# Switch_Board.net
KiCad netlist of a schematic drawn in Altium Designer
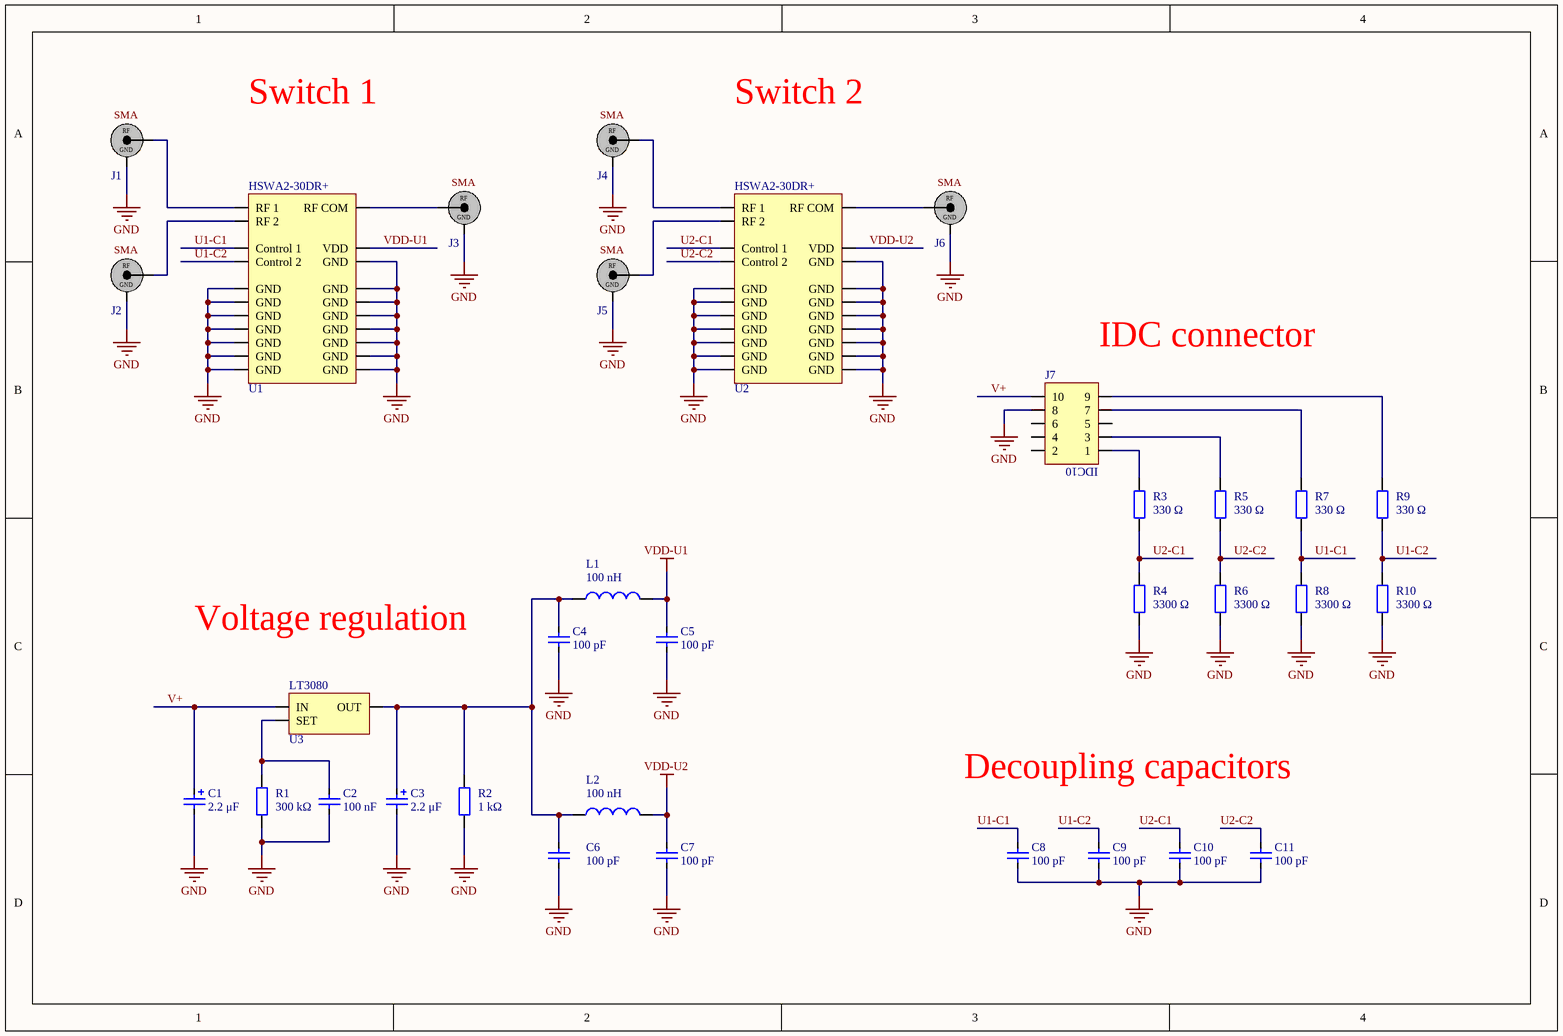
[diagram p0: Switch_Board.SchDoc]

(export (version "E")
  (design (tool "Eeschema 10.0.6"))
  (components
    (comp (ref "C1")
      (value "2.2 μF")
      (footprint "EIA 3528-21")
      (description "General symbol for a surface-mount polarized capacitor")
      (fields (field (name "Comment") "Capacitor (polarized)"))
      (libsource (lib "Switch_System") (part "Capacitor (polarized)"))
    )
    (comp (ref "C2")
      (value "100 nF")
      (footprint "0603C")
      (description "General symbol for a surface-mount capacitor")
      (fields (field (name "Comment") "Capacitor"))
      (libsource (lib "Switch_System") (part "Capacitor"))
    )
    (comp (ref "C3")
      (value "2.2 μF")
      (footprint "EIA 3528-21")
      (description "General symbol for a surface-mount polarized capacitor")
      (fields (field (name "Comment") "Capacitor (polarized)"))
      (libsource (lib "Switch_System") (part "Capacitor (polarized)"))
    )
    (comp (ref "C4")
      (value "100 pF")
      (footprint "0603C")
      (description "General symbol for a surface-mount capacitor")
      (fields (field (name "Comment") "Capacitor"))
      (libsource (lib "Switch_System") (part "Capacitor"))
    )
    (comp (ref "C5")
      (value "100 pF")
      (footprint "0603C")
      (description "General symbol for a surface-mount capacitor")
      (fields (field (name "Comment") "Capacitor"))
      (libsource (lib "Switch_System") (part "Capacitor"))
    )
    (comp (ref "C6")
      (value "100 pF")
      (footprint "0603C")
      (description "General symbol for a surface-mount capacitor")
      (fields (field (name "Comment") "Capacitor"))
      (libsource (lib "Switch_System") (part "Capacitor"))
    )
    (comp (ref "C7")
      (value "100 pF")
      (footprint "0603C")
      (description "General symbol for a surface-mount capacitor")
      (fields (field (name "Comment") "Capacitor"))
      (libsource (lib "Switch_System") (part "Capacitor"))
    )
    (comp (ref "C8")
      (value "100 pF")
      (footprint "0603C")
      (description "General symbol for a surface-mount capacitor")
      (fields (field (name "Comment") "Capacitor"))
      (libsource (lib "Switch_System") (part "Capacitor"))
    )
    (comp (ref "C9")
      (value "100 pF")
      (footprint "0603C")
      (description "General symbol for a surface-mount capacitor")
      (fields (field (name "Comment") "Capacitor"))
      (libsource (lib "Switch_System") (part "Capacitor"))
    )
    (comp (ref "C10")
      (value "100 pF")
      (footprint "0603C")
      (description "General symbol for a surface-mount capacitor")
      (fields (field (name "Comment") "Capacitor"))
      (libsource (lib "Switch_System") (part "Capacitor"))
    )
    (comp (ref "C11")
      (value "100 pF")
      (footprint "0603C")
      (description "General symbol for a surface-mount capacitor")
      (fields (field (name "Comment") "Capacitor"))
      (libsource (lib "Switch_System") (part "Capacitor"))
    )
    (comp (ref "J1")
      (value "SMA connector")
      (footprint "SMA edge connector")
      (description "SMA PCB jack")
      (libsource (lib "Switch_System") (part "SMA connector"))
    )
    (comp (ref "J2")
      (value "SMA connector")
      (footprint "SMA edge connector")
      (description "SMA PCB jack")
      (libsource (lib "Switch_System") (part "SMA connector"))
    )
    (comp (ref "J3")
      (value "SMA connector")
      (footprint "SMA edge connector")
      (description "SMA PCB jack")
      (libsource (lib "Switch_System") (part "SMA connector"))
    )
    (comp (ref "J4")
      (value "SMA connector")
      (footprint "SMA edge connector")
      (description "SMA PCB jack")
      (libsource (lib "Switch_System") (part "SMA connector"))
    )
    (comp (ref "J5")
      (value "SMA connector")
      (footprint "SMA edge connector")
      (description "SMA PCB jack")
      (libsource (lib "Switch_System") (part "SMA connector"))
    )
    (comp (ref "J6")
      (value "SMA connector")
      (footprint "SMA edge connector")
      (description "SMA PCB jack")
      (libsource (lib "Switch_System") (part "SMA connector"))
    )
    (comp (ref "J7")
      (value "IDC10")
      (footprint "IDC10")
      (description "IDC connector, 10 pin, right angle")
      (libsource (lib "Switch_Board") (part "IDC10"))
    )
    (comp (ref "L1")
      (value "100 nH")
      (footprint "0603I")
      (description "General symbol for a surface-mount inductor")
      (fields (field (name "Comment") "Inductor"))
      (libsource (lib "Switch_System") (part "Inductor"))
    )
    (comp (ref "L2")
      (value "100 nH")
      (footprint "0603I")
      (description "General symbol for a surface-mount inductor")
      (fields (field (name "Comment") "Inductor"))
      (libsource (lib "Switch_System") (part "Inductor"))
    )
    (comp (ref "R1")
      (value "300 kΩ")
      (footprint "0805")
      (description "General symbol for a surface-mount resistor")
      (fields (field (name "Comment") "Resistor"))
      (libsource (lib "Switch_System") (part "Resistor"))
    )
    (comp (ref "R2")
      (value "1 kΩ")
      (footprint "0805")
      (description "General symbol for a surface-mount resistor")
      (fields (field (name "Comment") "Resistor"))
      (libsource (lib "Switch_System") (part "Resistor"))
    )
    (comp (ref "R3")
      (value "330 Ω")
      (footprint "0805")
      (description "General symbol for a surface-mount resistor")
      (fields (field (name "Comment") "Resistor"))
      (libsource (lib "Switch_System") (part "Resistor"))
    )
    (comp (ref "R4")
      (value "3300 Ω")
      (footprint "0805")
      (description "General symbol for a surface-mount resistor")
      (fields (field (name "Comment") "Resistor"))
      (libsource (lib "Switch_System") (part "Resistor"))
    )
    (comp (ref "R5")
      (value "330 Ω")
      (footprint "0805")
      (description "General symbol for a surface-mount resistor")
      (fields (field (name "Comment") "Resistor"))
      (libsource (lib "Switch_System") (part "Resistor"))
    )
    (comp (ref "R6")
      (value "3300 Ω")
      (footprint "0805")
      (description "General symbol for a surface-mount resistor")
      (fields (field (name "Comment") "Resistor"))
      (libsource (lib "Switch_System") (part "Resistor"))
    )
    (comp (ref "R7")
      (value "330 Ω")
      (footprint "0805")
      (description "General symbol for a surface-mount resistor")
      (fields (field (name "Comment") "Resistor"))
      (libsource (lib "Switch_System") (part "Resistor"))
    )
    (comp (ref "R8")
      (value "3300 Ω")
      (footprint "0805")
      (description "General symbol for a surface-mount resistor")
      (fields (field (name "Comment") "Resistor"))
      (libsource (lib "Switch_System") (part "Resistor"))
    )
    (comp (ref "R9")
      (value "330 Ω")
      (footprint "0805")
      (description "General symbol for a surface-mount resistor")
      (fields (field (name "Comment") "Resistor"))
      (libsource (lib "Switch_System") (part "Resistor"))
    )
    (comp (ref "R10")
      (value "3300 Ω")
      (footprint "0805")
      (description "General symbol for a surface-mount resistor")
      (fields (field (name "Comment") "Resistor"))
      (libsource (lib "Switch_System") (part "Resistor"))
    )
    (comp (ref "U1")
      (value "HSWA2-30DR+")
      (footprint "DG983-1")
      (description "Mini-Circuits surface-mount RF switch")
      (libsource (lib "Switch_System") (part "HSWA2-30DR+"))
    )
    (comp (ref "U2")
      (value "HSWA2-30DR+")
      (footprint "DG983-1")
      (description "Mini-Circuits surface-mount RF switch")
      (libsource (lib "Switch_System") (part "HSWA2-30DR+"))
    )
    (comp (ref "U3")
      (value "LT3080")
      (footprint "SOT-223")
      (description "Linear Technology surface-mount adjustable voltage regulator")
      (libsource (lib "Switch_System") (part "LT3080"))
    )
  )
  (nets
    (net (code "1") (name "/U1-C1") (class "Default")
      (node (ref "C8") (pin "2") (pinfunction "2_2") (pintype "passive"))
      (node (ref "R7") (pin "1") (pinfunction "1_1") (pintype "passive"))
      (node (ref "R8") (pin "2") (pinfunction "2_2") (pintype "passive"))
      (node (ref "U1") (pin "17") (pinfunction "Control_1_17") (pintype "passive"))
    )
    (net (code "2") (name "/U1-C2") (class "Default")
      (node (ref "C9") (pin "2") (pinfunction "2_2") (pintype "passive"))
      (node (ref "R10") (pin "2") (pinfunction "2_2") (pintype "passive"))
      (node (ref "R9") (pin "1") (pinfunction "1_1") (pintype "passive"))
      (node (ref "U1") (pin "16") (pinfunction "Control_2_16") (pintype "passive"))
    )
    (net (code "3") (name "/U2-C1") (class "Default")
      (node (ref "C10") (pin "2") (pinfunction "2_2") (pintype "passive"))
      (node (ref "R3") (pin "1") (pinfunction "1_1") (pintype "passive"))
      (node (ref "R4") (pin "2") (pinfunction "2_2") (pintype "passive"))
      (node (ref "U2") (pin "17") (pinfunction "Control_1_17") (pintype "passive"))
    )
    (net (code "4") (name "/U2-C2") (class "Default")
      (node (ref "C11") (pin "2") (pinfunction "2_2") (pintype "passive"))
      (node (ref "R5") (pin "1") (pinfunction "1_1") (pintype "passive"))
      (node (ref "R6") (pin "2") (pinfunction "2_2") (pintype "passive"))
      (node (ref "U2") (pin "16") (pinfunction "Control_2_16") (pintype "passive"))
    )
    (net (code "5") (name "/V+") (class "Default")
      (node (ref "C1") (pin "1") (pinfunction "1_1") (pintype "passive"))
      (node (ref "J7") (pin "10") (pinfunction "10_10") (pintype "passive"))
      (node (ref "U3") (pin "IN") (pinfunction "IN_IN") (pintype "passive"))
    )
    (net (code "6") (name "GND") (class "Default")
      (node (ref "C1") (pin "2") (pinfunction "2_2") (pintype "passive"))
      (node (ref "C10") (pin "1") (pinfunction "1_1") (pintype "passive"))
      (node (ref "C11") (pin "1") (pinfunction "1_1") (pintype "passive"))
      (node (ref "C2") (pin "1") (pinfunction "1_1") (pintype "passive"))
      (node (ref "C3") (pin "2") (pinfunction "2_2") (pintype "passive"))
      (node (ref "C4") (pin "1") (pinfunction "1_1") (pintype "passive"))
      (node (ref "C5") (pin "1") (pinfunction "1_1") (pintype "passive"))
      (node (ref "C6") (pin "1") (pinfunction "1_1") (pintype "passive"))
      (node (ref "C7") (pin "1") (pinfunction "1_1") (pintype "passive"))
      (node (ref "C8") (pin "1") (pinfunction "1_1") (pintype "passive"))
      (node (ref "C9") (pin "1") (pinfunction "1_1") (pintype "passive"))
      (node (ref "J1") (pin "0") (pinfunction "GND_0") (pintype "passive"))
      (node (ref "J2") (pin "0") (pinfunction "GND_0") (pintype "passive"))
      (node (ref "J3") (pin "0") (pinfunction "GND_0") (pintype "passive"))
      (node (ref "J4") (pin "0") (pinfunction "GND_0") (pintype "passive"))
      (node (ref "J5") (pin "0") (pinfunction "GND_0") (pintype "passive"))
      (node (ref "J6") (pin "0") (pinfunction "GND_0") (pintype "passive"))
      (node (ref "J7") (pin "8") (pinfunction "8_8") (pintype "passive"))
      (node (ref "R1") (pin "1") (pinfunction "1_1") (pintype "passive"))
      (node (ref "R10") (pin "1") (pinfunction "1_1") (pintype "passive"))
      (node (ref "R2") (pin "1") (pinfunction "1_1") (pintype "passive"))
      (node (ref "R4") (pin "1") (pinfunction "1_1") (pintype "passive"))
      (node (ref "R6") (pin "1") (pinfunction "1_1") (pintype "passive"))
      (node (ref "R8") (pin "1") (pinfunction "1_1") (pintype "passive"))
      (node (ref "U1") (pin "1") (pinfunction "GND_1") (pintype "passive"))
      (node (ref "U1") (pin "10") (pinfunction "GND_10") (pintype "passive"))
      (node (ref "U1") (pin "11") (pinfunction "GND_11") (pintype "passive"))
      (node (ref "U1") (pin "12") (pinfunction "GND_12") (pintype "passive"))
      (node (ref "U1") (pin "14") (pinfunction "GND_14") (pintype "passive"))
      (node (ref "U1") (pin "15") (pinfunction "GND_15") (pintype "passive"))
      (node (ref "U1") (pin "18") (pinfunction "GND_18") (pintype "passive"))
      (node (ref "U1") (pin "19") (pinfunction "GND_19") (pintype "passive"))
      (node (ref "U1") (pin "2") (pinfunction "GND_2") (pintype "passive"))
      (node (ref "U1") (pin "4") (pinfunction "GND_4") (pintype "passive"))
      (node (ref "U1") (pin "5") (pinfunction "GND_5") (pintype "passive"))
      (node (ref "U1") (pin "6") (pinfunction "GND_6") (pintype "passive"))
      (node (ref "U1") (pin "7") (pinfunction "GND_7") (pintype "passive"))
      (node (ref "U1") (pin "9") (pinfunction "GND_9") (pintype "passive"))
      (node (ref "U1") (pin "GND") (pinfunction "GND_GND") (pintype "passive"))
      (node (ref "U2") (pin "1") (pinfunction "GND_1") (pintype "passive"))
      (node (ref "U2") (pin "10") (pinfunction "GND_10") (pintype "passive"))
      (node (ref "U2") (pin "11") (pinfunction "GND_11") (pintype "passive"))
      (node (ref "U2") (pin "12") (pinfunction "GND_12") (pintype "passive"))
      (node (ref "U2") (pin "14") (pinfunction "GND_14") (pintype "passive"))
      (node (ref "U2") (pin "15") (pinfunction "GND_15") (pintype "passive"))
      (node (ref "U2") (pin "18") (pinfunction "GND_18") (pintype "passive"))
      (node (ref "U2") (pin "19") (pinfunction "GND_19") (pintype "passive"))
      (node (ref "U2") (pin "2") (pinfunction "GND_2") (pintype "passive"))
      (node (ref "U2") (pin "4") (pinfunction "GND_4") (pintype "passive"))
      (node (ref "U2") (pin "5") (pinfunction "GND_5") (pintype "passive"))
      (node (ref "U2") (pin "6") (pinfunction "GND_6") (pintype "passive"))
      (node (ref "U2") (pin "7") (pinfunction "GND_7") (pintype "passive"))
      (node (ref "U2") (pin "9") (pinfunction "GND_9") (pintype "passive"))
      (node (ref "U2") (pin "GND") (pinfunction "GND_GND") (pintype "passive"))
    )
    (net (code "7") (name "Net-(C2-Pad2)") (class "Default")
      (node (ref "C2") (pin "2") (pinfunction "2_2") (pintype "passive"))
      (node (ref "R1") (pin "2") (pinfunction "2_2") (pintype "passive"))
      (node (ref "U3") (pin "SET") (pinfunction "SET_SET") (pintype "passive"))
    )
    (net (code "8") (name "Net-(C3-Pad1)") (class "Default")
      (node (ref "C3") (pin "1") (pinfunction "1_1") (pintype "passive"))
      (node (ref "C4") (pin "2") (pinfunction "2_2") (pintype "passive"))
      (node (ref "C6") (pin "2") (pinfunction "2_2") (pintype "passive"))
      (node (ref "L1") (pin "1") (pinfunction "1_1") (pintype "passive"))
      (node (ref "L2") (pin "1") (pinfunction "1_1") (pintype "passive"))
      (node (ref "R2") (pin "2") (pinfunction "2_2") (pintype "passive"))
      (node (ref "U3") (pin "OUT") (pinfunction "OUT_OUT") (pintype "passive"))
    )
    (net (code "9") (name "Net-(J1-RF)") (class "Default")
      (node (ref "J1") (pin "1") (pinfunction "RF_1") (pintype "passive"))
      (node (ref "U1") (pin "3") (pinfunction "RF_1_3") (pintype "passive"))
    )
    (net (code "10") (name "Net-(J2-RF)") (class "Default")
      (node (ref "J2") (pin "1") (pinfunction "RF_1") (pintype "passive"))
      (node (ref "U1") (pin "13") (pinfunction "RF_2_13") (pintype "passive"))
    )
    (net (code "11") (name "Net-(J3-RF)") (class "Default")
      (node (ref "J3") (pin "1") (pinfunction "RF_1") (pintype "passive"))
      (node (ref "U1") (pin "8") (pinfunction "RF_COM_8") (pintype "passive"))
    )
    (net (code "12") (name "Net-(J4-RF)") (class "Default")
      (node (ref "J4") (pin "1") (pinfunction "RF_1") (pintype "passive"))
      (node (ref "U2") (pin "3") (pinfunction "RF_1_3") (pintype "passive"))
    )
    (net (code "13") (name "Net-(J5-RF)") (class "Default")
      (node (ref "J5") (pin "1") (pinfunction "RF_1") (pintype "passive"))
      (node (ref "U2") (pin "13") (pinfunction "RF_2_13") (pintype "passive"))
    )
    (net (code "14") (name "Net-(J6-RF)") (class "Default")
      (node (ref "J6") (pin "1") (pinfunction "RF_1") (pintype "passive"))
      (node (ref "U2") (pin "8") (pinfunction "RF_COM_8") (pintype "passive"))
    )
    (net (code "15") (name "Net-(J7-Pad1)") (class "Default")
      (node (ref "J7") (pin "1") (pinfunction "1_1") (pintype "passive"))
      (node (ref "R3") (pin "2") (pinfunction "2_2") (pintype "passive"))
    )
    (net (code "16") (name "Net-(J7-Pad3)") (class "Default")
      (node (ref "J7") (pin "3") (pinfunction "3_3") (pintype "passive"))
      (node (ref "R5") (pin "2") (pinfunction "2_2") (pintype "passive"))
    )
    (net (code "17") (name "Net-(J7-Pad7)") (class "Default")
      (node (ref "J7") (pin "7") (pinfunction "7_7") (pintype "passive"))
      (node (ref "R7") (pin "2") (pinfunction "2_2") (pintype "passive"))
    )
    (net (code "18") (name "Net-(J7-Pad9)") (class "Default")
      (node (ref "J7") (pin "9") (pinfunction "9_9") (pintype "passive"))
      (node (ref "R9") (pin "2") (pinfunction "2_2") (pintype "passive"))
    )
    (net (code "19") (name "VDD-U1") (class "Default")
      (node (ref "C5") (pin "2") (pinfunction "2_2") (pintype "passive"))
      (node (ref "L1") (pin "2") (pinfunction "2_2") (pintype "passive"))
      (node (ref "U1") (pin "20") (pinfunction "VDD_20") (pintype "passive"))
    )
    (net (code "20") (name "VDD-U2") (class "Default")
      (node (ref "C7") (pin "2") (pinfunction "2_2") (pintype "passive"))
      (node (ref "L2") (pin "2") (pinfunction "2_2") (pintype "passive"))
      (node (ref "U2") (pin "20") (pinfunction "VDD_20") (pintype "passive"))
    )
    (net (code "21") (name "unconnected-(J7-Pad2)") (class "Default")
      (node (ref "J7") (pin "2") (pinfunction "2_2") (pintype "passive"))
    )
    (net (code "22") (name "unconnected-(J7-Pad4)") (class "Default")
      (node (ref "J7") (pin "4") (pinfunction "4_4") (pintype "passive"))
    )
    (net (code "23") (name "unconnected-(J7-Pad5)") (class "Default")
      (node (ref "J7") (pin "5") (pinfunction "5_5") (pintype "passive"))
    )
    (net (code "24") (name "unconnected-(J7-Pad6)") (class "Default")
      (node (ref "J7") (pin "6") (pinfunction "6_6") (pintype "passive"))
    )
  )
)
